# RiskChemi_Sensors_V2_04M1.net
KiCad netlist of a schematic drawn in Altium Designer
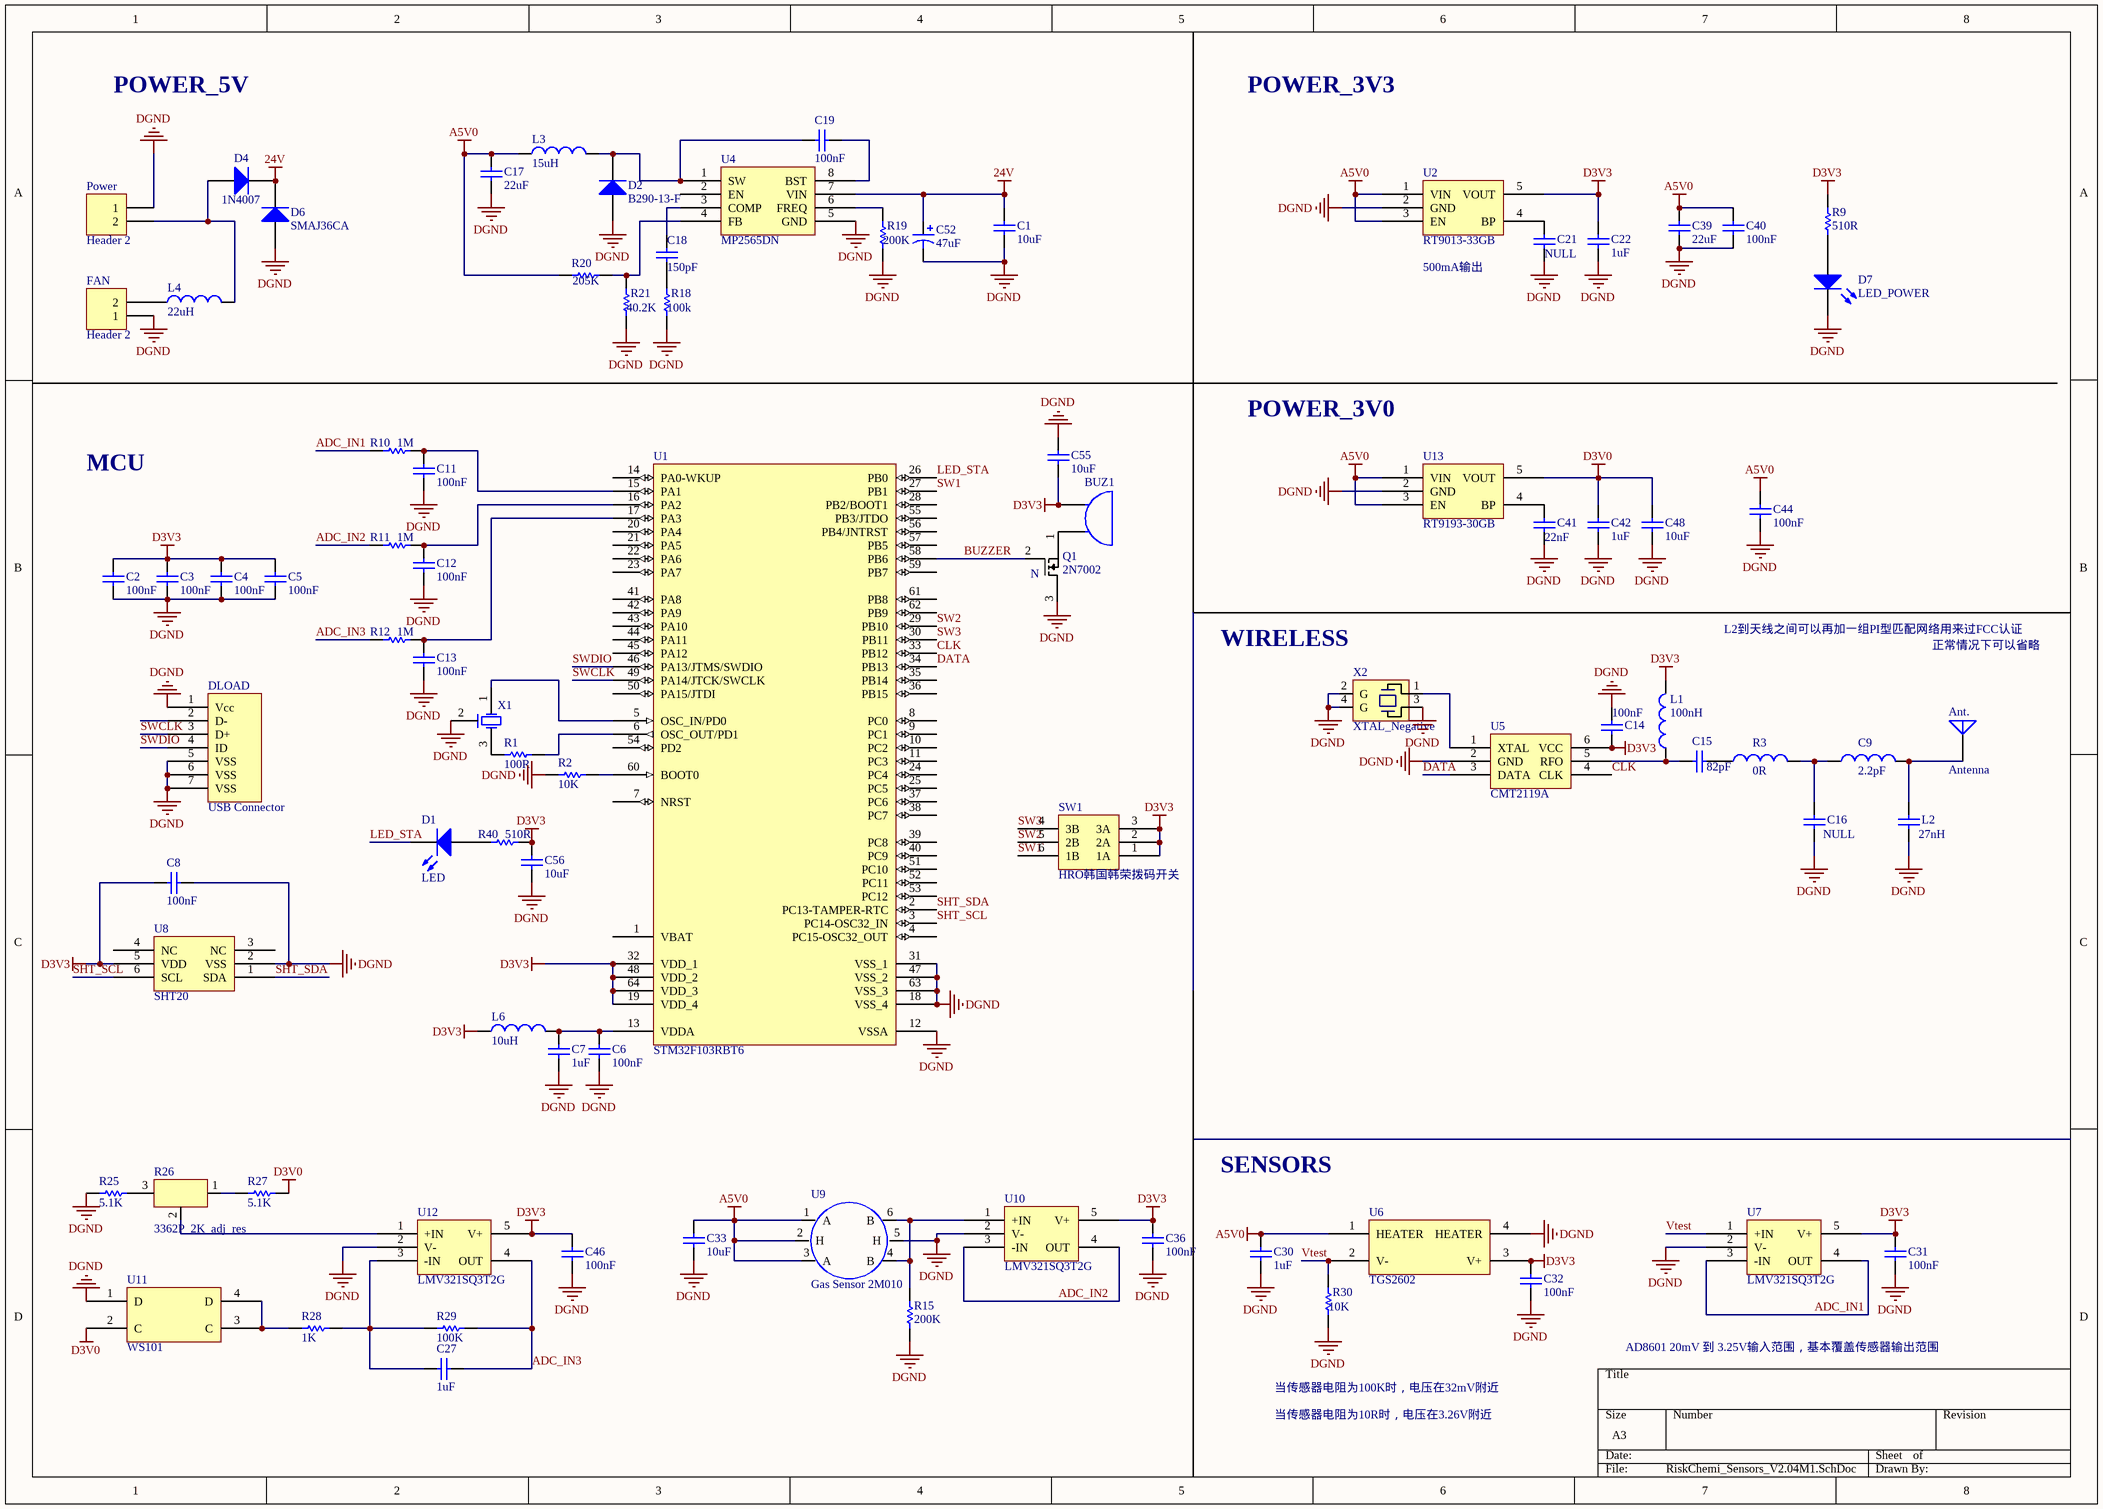
[diagram p0: RiskChemi_Sensors_V2.04M1.SchDoc]

(export (version "E")
  (design (tool "Eeschema 10.0.6"))
  (components
    (comp (ref "Ant.")
      (value "Antenna")
      (footprint "PIN1")
      (description "Generic Antenna")
      (fields (field (name "PUBLISHER") "Altium Limited"))
      (libsource (lib "Miscellaneous Devices") (part "Antenna"))
    )
    (comp (ref "BUZ1")
      (value "BUZZER 0905 through hole")
      (footprint "BUZ0905")
      (description "Buzzer")
      (libsource (lib "杂元件库") (part "BUZZER"))
    )
    (comp (ref "C1")
      (value "10uF")
      (footprint "0805")
      (description "Capacitor,50V")
      (fields (field (name "PUBLISHER") "Altium Limited"))
      (libsource (lib "Miscellaneous Devices") (part "Cap"))
    )
    (comp (ref "C2")
      (value "100nF")
      (footprint "BinFeng:0603")
      (description "Capacitor")
      (fields (field (name "PUBLISHER") "Altium Limited"))
      (libsource (lib "Miscellaneous Devices") (part "Cap"))
    )
    (comp (ref "C3")
      (value "100nF")
      (footprint "BinFeng:0603")
      (description "Capacitor")
      (fields (field (name "PUBLISHER") "Altium Limited"))
      (libsource (lib "Miscellaneous Devices") (part "Cap"))
    )
    (comp (ref "C4")
      (value "100nF")
      (footprint "BinFeng:0603")
      (description "Capacitor")
      (fields (field (name "PUBLISHER") "Altium Limited"))
      (libsource (lib "Miscellaneous Devices") (part "Cap"))
    )
    (comp (ref "C5")
      (value "100nF")
      (footprint "BinFeng:0603")
      (description "Capacitor")
      (fields (field (name "PUBLISHER") "Altium Limited"))
      (libsource (lib "Miscellaneous Devices") (part "Cap"))
    )
    (comp (ref "C6")
      (value "100nF")
      (footprint "BinFeng:0603")
      (description "Capacitor")
      (fields (field (name "PUBLISHER") "Altium Limited"))
      (libsource (lib "Miscellaneous Devices") (part "Cap"))
    )
    (comp (ref "C7")
      (value "1uF")
      (footprint "BinFeng:0603")
      (description "Capacitor")
      (fields (field (name "PUBLISHER") "Altium Limited"))
      (libsource (lib "Miscellaneous Devices") (part "Cap"))
    )
    (comp (ref "C8")
      (value "100nF")
      (footprint "BinFeng:0603")
      (description "Capacitor")
      (fields (field (name "PUBLISHER") "Altium Limited"))
      (libsource (lib "Miscellaneous Devices") (part "Cap"))
    )
    (comp (ref "C9")
      (value "2.2pF")
      (footprint "0603C")
      (description "Inductor")
      (fields (field (name "PUBLISHER") "Altium Limited"))
      (libsource (lib "Miscellaneous Devices") (part "Inductor"))
    )
    (comp (ref "C11")
      (value "100nF")
      (footprint "BinFeng:0603")
      (description "Capacitor")
      (fields (field (name "PUBLISHER") "Altium Limited"))
      (libsource (lib "Miscellaneous Devices") (part "Cap"))
    )
    (comp (ref "C12")
      (value "100nF")
      (footprint "BinFeng:0603")
      (description "Capacitor")
      (fields (field (name "PUBLISHER") "Altium Limited"))
      (libsource (lib "Miscellaneous Devices") (part "Cap"))
    )
    (comp (ref "C13")
      (value "100nF")
      (footprint "BinFeng:0603")
      (description "Capacitor")
      (fields (field (name "PUBLISHER") "Altium Limited"))
      (libsource (lib "Miscellaneous Devices") (part "Cap"))
    )
    (comp (ref "C14")
      (value "100nF")
      (footprint "BinFeng:0402")
      (description "Capacitor")
      (fields (field (name "PUBLISHER") "Altium Limited"))
      (libsource (lib "Miscellaneous Devices") (part "Cap"))
    )
    (comp (ref "C15")
      (value "82pF")
      (footprint "BinFeng:0402")
      (description "Capacitor")
      (fields (field (name "PUBLISHER") "Altium Limited"))
      (libsource (lib "Miscellaneous Devices") (part "Cap"))
    )
    (comp (ref "C16")
      (value "NULL")
      (footprint "BinFeng:0402")
      (description "Capacitor")
      (fields (field (name "PUBLISHER") "Altium Limited"))
      (libsource (lib "Miscellaneous Devices") (part "Cap"))
    )
    (comp (ref "C17")
      (value "22uF")
      (footprint "0805")
      (description "Capacitor,50V")
      (fields (field (name "PUBLISHER") "Altium Limited"))
      (libsource (lib "Miscellaneous Devices") (part "Cap"))
    )
    (comp (ref "C18")
      (value "150pF")
      (footprint "BinFeng:0603")
      (description "Capacitor")
      (fields (field (name "PUBLISHER") "Altium Limited"))
      (libsource (lib "Miscellaneous Devices") (part "Cap"))
    )
    (comp (ref "C19")
      (value "100nF")
      (footprint "BinFeng:0603")
      (description "Capacitor")
      (fields (field (name "PUBLISHER") "Altium Limited"))
      (libsource (lib "Miscellaneous Devices") (part "Cap"))
    )
    (comp (ref "C21")
      (value "NULL")
      (footprint "BinFeng:0402")
      (description "Capacitor")
      (fields (field (name "PUBLISHER") "Altium Limited"))
      (libsource (lib "Miscellaneous Devices") (part "Cap"))
    )
    (comp (ref "C22")
      (value "1uF")
      (footprint "BinFeng:0402")
      (description "Capacitor")
      (fields (field (name "PUBLISHER") "Altium Limited"))
      (libsource (lib "Miscellaneous Devices") (part "Cap"))
    )
    (comp (ref "C27")
      (value "1uF")
      (footprint "BinFeng:0603")
      (description "Capacitor")
      (fields (field (name "PUBLISHER") "Altium Limited"))
      (libsource (lib "Miscellaneous Devices") (part "Cap"))
    )
    (comp (ref "C30")
      (value "1uF")
      (footprint "BinFeng:0603")
      (description "Capacitor")
      (fields (field (name "PUBLISHER") "Altium Limited"))
      (libsource (lib "Miscellaneous Devices") (part "Cap"))
    )
    (comp (ref "C31")
      (value "100nF")
      (footprint "BinFeng:0603")
      (description "Capacitor")
      (fields (field (name "PUBLISHER") "Altium Limited"))
      (libsource (lib "Miscellaneous Devices") (part "Cap"))
    )
    (comp (ref "C32")
      (value "100nF")
      (footprint "BinFeng:0603")
      (description "Capacitor")
      (fields (field (name "PUBLISHER") "Altium Limited"))
      (libsource (lib "Miscellaneous Devices") (part "Cap"))
    )
    (comp (ref "C33")
      (value "10uF")
      (footprint "0805")
      (description "Capacitor")
      (fields (field (name "PUBLISHER") "Altium Limited"))
      (libsource (lib "Miscellaneous Devices") (part "Cap"))
    )
    (comp (ref "C36")
      (value "100nF")
      (footprint "BinFeng:0603")
      (description "Capacitor")
      (fields (field (name "PUBLISHER") "Altium Limited"))
      (libsource (lib "Miscellaneous Devices") (part "Cap"))
    )
    (comp (ref "C39")
      (value "22uF")
      (footprint "1206")
      (description "Capacitor")
      (fields (field (name "PUBLISHER") "Altium Limited"))
      (libsource (lib "Miscellaneous Devices") (part "Cap"))
    )
    (comp (ref "C40")
      (value "100nF")
      (footprint "BinFeng:0402")
      (description "Capacitor")
      (fields (field (name "PUBLISHER") "Altium Limited"))
      (libsource (lib "Miscellaneous Devices") (part "Cap"))
    )
    (comp (ref "C41")
      (value "22nF")
      (footprint "BinFeng:0402")
      (description "Capacitor")
      (fields (field (name "PUBLISHER") "Altium Limited"))
      (libsource (lib "Miscellaneous Devices") (part "Cap"))
    )
    (comp (ref "C42")
      (value "1uF")
      (footprint "BinFeng:0402")
      (description "Capacitor")
      (fields (field (name "PUBLISHER") "Altium Limited"))
      (libsource (lib "Miscellaneous Devices") (part "Cap"))
    )
    (comp (ref "C44")
      (value "100nF")
      (footprint "BinFeng:0402")
      (description "Capacitor")
      (fields (field (name "PUBLISHER") "Altium Limited"))
      (libsource (lib "Miscellaneous Devices") (part "Cap"))
    )
    (comp (ref "C46")
      (value "100nF")
      (footprint "BinFeng:0603")
      (description "Capacitor")
      (fields (field (name "PUBLISHER") "Altium Limited"))
      (libsource (lib "Miscellaneous Devices") (part "Cap"))
    )
    (comp (ref "C48")
      (value "10uF")
      (footprint "0805")
      (description "Capacitor")
      (fields (field (name "PUBLISHER") "Altium Limited"))
      (libsource (lib "Miscellaneous Devices") (part "Cap"))
    )
    (comp (ref "C52")
      (value "47uF")
      (footprint "cap_pol_8*10.2")
      (description "Polarized Capacitor (Radial)")
      (fields (field (name "PUBLISHER") "Altium Limited"))
      (libsource (lib "Miscellaneous Devices") (part "Cap Pol1"))
    )
    (comp (ref "C55")
      (value "10uF")
      (footprint "0805")
      (description "Capacitor")
      (fields (field (name "PUBLISHER") "Altium Limited"))
      (libsource (lib "Miscellaneous Devices") (part "Cap"))
    )
    (comp (ref "C56")
      (value "10uF")
      (footprint "0805")
      (description "Capacitor")
      (fields (field (name "PUBLISHER") "Altium Limited"))
      (libsource (lib "Miscellaneous Devices") (part "Cap"))
    )
    (comp (ref "D1")
      (value "LED")
      (footprint "1206_LED")
      (description "Typical INFRARED GaAs LED")
      (fields (field (name "PUBLISHER") "Altium Limited"))
      (libsource (lib "Miscellaneous Devices") (part "LED0"))
    )
    (comp (ref "D2")
      (value "B290-13-F")
      (footprint "B290")
      (description "Default Diode")
      (fields (field (name "PUBLISHER") "Altium Limited"))
      (libsource (lib "Miscellaneous Devices") (part "Diode"))
    )
    (comp (ref "D4")
      (value "1N4007")
      (footprint "6032_pol")
      (description "1 Amp General Purpose Rectifier")
      (fields (field (name "PUBLISHER") "Altium Limited"))
      (libsource (lib "Miscellaneous Devices") (part "Diode 1N4007"))
    )
    (comp (ref "D6")
      (value "SMAJ36CA")
      (footprint "B290")
      (description "1 Amp General Purpose Rectifier")
      (fields (field (name "PUBLISHER") "Altium Limited"))
      (libsource (lib "Miscellaneous Devices") (part "Diode 1N4007"))
    )
    (comp (ref "D7")
      (value "LED_POWER")
      (footprint "1206_LED")
      (description "Typical INFRARED GaAs LED")
      (fields (field (name "PUBLISHER") "Altium Limited"))
      (libsource (lib "Miscellaneous Devices") (part "LED0"))
    )
    (comp (ref "DLOAD")
      (value "USB Connector")
      (footprint "Mini_USB")
      (libsource (lib "BinFeng_Connectors") (part "Component_1"))
    )
    (comp (ref "FAN")
      (value "Header 2")
      (footprint "HDR1X2")
      (description "Header, 2-Pin")
      (fields (field (name "PUBLISHER") "Altium Limited"))
      (libsource (lib "Miscellaneous Connectors") (part "Header 2"))
    )
    (comp (ref "L1")
      (value "100nH")
      (footprint "0603C")
      (description "Inductor")
      (fields (field (name "PUBLISHER") "Altium Limited"))
      (libsource (lib "Miscellaneous Devices") (part "Inductor"))
    )
    (comp (ref "L2")
      (value "27nH")
      (footprint "BinFeng:0402")
      (description "Capacitor")
      (fields (field (name "PUBLISHER") "Altium Limited"))
      (libsource (lib "Miscellaneous Devices") (part "Cap"))
    )
    (comp (ref "L3")
      (value "15uH")
      (footprint "4*4 Inductor")
      (description "Inductor, 1A")
      (fields (field (name "PUBLISHER") "Altium Limited"))
      (libsource (lib "Miscellaneous Devices") (part "Inductor"))
    )
    (comp (ref "L4")
      (value "22uH")
      (footprint "10*10Inductor")
      (description "Inductor, 1A")
      (fields (field (name "PUBLISHER") "Altium Limited"))
      (libsource (lib "Miscellaneous Devices") (part "Inductor"))
    )
    (comp (ref "L6")
      (value "10uH")
      (footprint "0805")
      (description "Inductor")
      (fields (field (name "PUBLISHER") "Altium Limited"))
      (libsource (lib "Miscellaneous Devices") (part "Inductor"))
    )
    (comp (ref "Power")
      (value "Header 2")
      (footprint "HDR1X2")
      (description "Header, 2-Pin")
      (fields (field (name "PUBLISHER") "Altium Limited"))
      (libsource (lib "") (part "Header 2_1"))
    )
    (comp (ref "Q1") (value "2N7002") (footprint "2N7002") (libsource (lib "seeder") (part "N-MOSFET")))
    (comp (ref "R1")
      (value "100R")
      (footprint "BinFeng:0603")
      (description "Resistor")
      (fields (field (name "PUBLISHER") "Altium Limited"))
      (libsource (lib "Miscellaneous Devices") (part "Res1"))
    )
    (comp (ref "R2")
      (value "10K")
      (footprint "BinFeng:0603")
      (description "Resistor")
      (fields (field (name "PUBLISHER") "Altium Limited"))
      (libsource (lib "Miscellaneous Devices") (part "Res1"))
    )
    (comp (ref "R3")
      (value "0R")
      (footprint "0603C")
      (description "Inductor")
      (fields (field (name "PUBLISHER") "Altium Limited"))
      (libsource (lib "Miscellaneous Devices") (part "Inductor"))
    )
    (comp (ref "R9")
      (value "510R")
      (footprint "BinFeng:0603")
      (description "Resistor")
      (fields (field (name "PUBLISHER") "Altium Limited"))
      (libsource (lib "Miscellaneous Devices") (part "Res1"))
    )
    (comp (ref "R10")
      (value "1M")
      (footprint "BinFeng:0603")
      (description "Resistor")
      (fields (field (name "PUBLISHER") "Altium Limited"))
      (libsource (lib "Miscellaneous Devices") (part "Res1"))
    )
    (comp (ref "R11")
      (value "1M")
      (footprint "BinFeng:0603")
      (description "Resistor")
      (fields (field (name "PUBLISHER") "Altium Limited"))
      (libsource (lib "Miscellaneous Devices") (part "Res1"))
    )
    (comp (ref "R12")
      (value "1M")
      (footprint "BinFeng:0603")
      (description "Resistor")
      (fields (field (name "PUBLISHER") "Altium Limited"))
      (libsource (lib "Miscellaneous Devices") (part "Res1"))
    )
    (comp (ref "R15")
      (value "200K")
      (footprint "BinFeng:0603C")
      (description "Resistor")
      (fields (field (name "Comment") "Res1") (field (name "PUBLISHER") "Altium Limited"))
      (libsource (lib "Miscellaneous Devices") (part "Res1"))
    )
    (comp (ref "R18")
      (value "100k")
      (footprint "BinFeng:0603")
      (description "Resistor")
      (fields (field (name "PUBLISHER") "Altium Limited"))
      (libsource (lib "Miscellaneous Devices") (part "Res1"))
    )
    (comp (ref "R19")
      (value "200K")
      (footprint "BinFeng:0402")
      (description "Resistor")
      (fields (field (name "PUBLISHER") "Altium Limited"))
      (libsource (lib "Miscellaneous Devices") (part "Res1"))
    )
    (comp (ref "R20")
      (value "205K")
      (footprint "BinFeng:0603")
      (description "Resistor")
      (fields (field (name "PUBLISHER") "Altium Limited"))
      (libsource (lib "Miscellaneous Devices") (part "Res1"))
    )
    (comp (ref "R21")
      (value "40.2K")
      (footprint "BinFeng:0603")
      (description "Resistor")
      (fields (field (name "PUBLISHER") "Altium Limited"))
      (libsource (lib "Miscellaneous Devices") (part "Res1"))
    )
    (comp (ref "R25")
      (value "5.1K")
      (footprint "BinFeng:0603")
      (description "Resistor")
      (fields (field (name "PUBLISHER") "Altium Limited"))
      (libsource (lib "Miscellaneous Devices") (part "Res1"))
    )
    (comp (ref "R26")
      (value "3362P_2K_adj_res")
      (footprint "res_adj")
      (libsource (lib "BinFeng_IC") (part "res_adj"))
    )
    (comp (ref "R27")
      (value "5.1K")
      (footprint "BinFeng:0603")
      (description "Resistor")
      (fields (field (name "PUBLISHER") "Altium Limited"))
      (libsource (lib "Miscellaneous Devices") (part "Res1"))
    )
    (comp (ref "R28")
      (value "1K")
      (footprint "BinFeng:0603")
      (description "Resistor")
      (fields (field (name "PUBLISHER") "Altium Limited"))
      (libsource (lib "Miscellaneous Devices") (part "Res1"))
    )
    (comp (ref "R29")
      (value "100K")
      (footprint "BinFeng:0603")
      (description "Resistor")
      (fields (field (name "PUBLISHER") "Altium Limited"))
      (libsource (lib "Miscellaneous Devices") (part "Res1"))
    )
    (comp (ref "R30")
      (value "10K")
      (footprint "BinFeng:0603")
      (description "Resistor")
      (fields (field (name "PUBLISHER") "Altium Limited"))
      (libsource (lib "Miscellaneous Devices") (part "Res1"))
    )
    (comp (ref "R40")
      (value "510R")
      (footprint "BinFeng:0603")
      (description "Resistor")
      (fields (field (name "PUBLISHER") "Altium Limited"))
      (libsource (lib "Miscellaneous Devices") (part "Res1"))
    )
    (comp (ref "SW1")
      (value "HRO韩国韩荣拨码开关")
      (footprint "SW_6P_HRO")
      (libsource (lib "BinFeng_IC") (part "SW_6P"))
    )
    (comp (ref "U1")
      (value "STM32F103RBT6")
      (footprint "LQFP64_N")
      (description "STM32 ARM-based 32-bit MCU with 64 Kbytes Flash, 64-pin LQFP, Industrial Temperature")
      (fields (field (name "PUBLISHER") "Altium Limited"))
      (libsource (lib "ST Microcontroller 32-Bit STM32") (part "STM32F103R8T6"))
    )
    (comp (ref "U2")
      (value "RT9013-33GB")
      (footprint "SOT-23-5")
      (libsource (lib "BinFeng_IC") (part "RT9193"))
    )
    (comp (ref "U4")
      (value "MP2565DN")
      (footprint "so-8")
      (description "DCDC 4.5V~28V input 1.8V ~5V output low power")
      (libsource (lib "BinFeng_IC") (part "MP1584"))
    )
    (comp (ref "U5")
      (value "CMT2119A")
      (footprint "sot23-6")
      (libsource (lib "BinFeng_IC") (part "CMT2119A"))
    )
    (comp (ref "U6")
      (value "TGS2602")
      (footprint "Gas Sensor TGS2602 Slot")
      (description "VOC sensor")
      (libsource (lib "BinFeng_IC") (part "TGS2602"))
    )
    (comp (ref "U7")
      (value "LMV321SQ3T2G")
      (footprint "SC-70-5")
      (libsource (lib "BinFeng_IC") (part "LMV321SQ3T2G"))
    )
    (comp (ref "U8") (value "SHT20") (footprint "SHT20") (libsource (lib "BinFeng_IC") (part "SHT20")))
    (comp (ref "U9")
      (value "Gas Sensor 2M010")
      (footprint "Gas Sensor 2M010 Slot")
      (libsource (lib "BinFeng_IC") (part "Gas Sensor"))
    )
    (comp (ref "U10")
      (value "LMV321SQ3T2G")
      (footprint "SC-70-5")
      (libsource (lib "BinFeng_IC") (part "LMV321SQ3T2G"))
    )
    (comp (ref "U11")
      (value "WS101")
      (footprint "Gas_Sensor_WS101_Slot")
      (libsource (lib "BinFeng_IC") (part "Gas Sensor_WS101"))
    )
    (comp (ref "U12")
      (value "LMV321SQ3T2G")
      (footprint "SC-70-5")
      (libsource (lib "BinFeng_IC") (part "LMV321SQ3T2G"))
    )
    (comp (ref "U13")
      (value "RT9193-30GB")
      (footprint "SOT-23-5")
      (libsource (lib "BinFeng_IC") (part "RT9193"))
    )
    (comp (ref "X1") (value "8M smd") (footprint "8Mhz_XTAL") (libsource (lib "Schlib1") (part "8M smd")))
    (comp (ref "X2")
      (value "XTAL_Negative")
      (footprint "XTAL3225")
      (libsource (lib "BinFeng_IC") (part "XTAL_Negative"))
    )
  )
  (nets
    (net (code "1") (name "/ADC_IN1") (class "Default")
      (node (ref "R10") (pin "1") (pinfunction "1_1") (pintype "passive"))
      (node (ref "U7") (pin "3") (pinfunction "-IN_3") (pintype "passive"))
      (node (ref "U7") (pin "4") (pinfunction "OUT_4") (pintype "passive"))
    )
    (net (code "2") (name "/ADC_IN2") (class "Default")
      (node (ref "R11") (pin "1") (pinfunction "1_1") (pintype "passive"))
      (node (ref "U10") (pin "3") (pinfunction "-IN_3") (pintype "passive"))
      (node (ref "U10") (pin "4") (pinfunction "OUT_4") (pintype "passive"))
    )
    (net (code "3") (name "/ADC_IN3") (class "Default")
      (node (ref "C27") (pin "1") (pinfunction "1_1") (pintype "passive"))
      (node (ref "R12") (pin "1") (pinfunction "1_1") (pintype "passive"))
      (node (ref "R29") (pin "2") (pinfunction "2_2") (pintype "passive"))
      (node (ref "U12") (pin "4") (pinfunction "OUT_4") (pintype "passive"))
    )
    (net (code "4") (name "/BUZZER") (class "Default")
      (node (ref "Q1") (pin "2") (pinfunction "G_2") (pintype "passive"))
      (node (ref "U1") (pin "58") (pinfunction "PB6_58") (pintype "bidirectional"))
    )
    (net (code "5") (name "/CLK") (class "Default")
      (node (ref "U1") (pin "33") (pinfunction "PB12_33") (pintype "bidirectional"))
      (node (ref "U5") (pin "4") (pinfunction "CLK_4") (pintype "passive"))
    )
    (net (code "6") (name "/DATA") (class "Default")
      (node (ref "U1") (pin "34") (pinfunction "PB13_34") (pintype "bidirectional"))
      (node (ref "U5") (pin "3") (pinfunction "DATA_3") (pintype "passive"))
    )
    (net (code "7") (name "/LED_STA") (class "Default")
      (node (ref "D1") (pin "2") (pinfunction "K_2") (pintype "passive"))
      (node (ref "U1") (pin "26") (pinfunction "PB0_26") (pintype "bidirectional"))
    )
    (net (code "8") (name "/SHT_SCL") (class "Default")
      (node (ref "U1") (pin "3") (pinfunction "PC14-OSC32_IN_3") (pintype "bidirectional"))
      (node (ref "U8") (pin "6") (pinfunction "SCL_6") (pintype "passive"))
    )
    (net (code "9") (name "/SHT_SDA") (class "Default")
      (node (ref "U1") (pin "2") (pinfunction "PC13-TAMPER-RTC_2") (pintype "bidirectional"))
      (node (ref "U8") (pin "1") (pinfunction "SDA_1") (pintype "passive"))
    )
    (net (code "10") (name "/SW1") (class "Default")
      (node (ref "SW1") (pin "6") (pinfunction "1B_6") (pintype "passive"))
      (node (ref "U1") (pin "27") (pinfunction "PB1_27") (pintype "bidirectional"))
    )
    (net (code "11") (name "/SW2") (class "Default")
      (node (ref "SW1") (pin "5") (pinfunction "2B_5") (pintype "passive"))
      (node (ref "U1") (pin "29") (pinfunction "PB10_29") (pintype "bidirectional"))
    )
    (net (code "12") (name "/SW3") (class "Default")
      (node (ref "SW1") (pin "4") (pinfunction "3B_4") (pintype "passive"))
      (node (ref "U1") (pin "30") (pinfunction "PB11_30") (pintype "bidirectional"))
    )
    (net (code "13") (name "/SWCLK") (class "Default")
      (node (ref "DLOAD") (pin "3") (pinfunction "D+_3") (pintype "passive"))
      (node (ref "U1") (pin "49") (pinfunction "PA14/JTCK/SWCLK_49") (pintype "bidirectional"))
    )
    (net (code "14") (name "/SWDIO") (class "Default")
      (node (ref "DLOAD") (pin "4") (pinfunction "ID_4") (pintype "passive"))
      (node (ref "U1") (pin "46") (pinfunction "PA13/JTMS/SWDIO_46") (pintype "bidirectional"))
    )
    (net (code "15") (name "/Vtest") (class "Default")
      (node (ref "R30") (pin "2") (pinfunction "2_2") (pintype "passive"))
      (node (ref "U6") (pin "2") (pinfunction "V-_2") (pintype "passive"))
      (node (ref "U7") (pin "1") (pinfunction "+IN_1") (pintype "passive"))
    )
    (net (code "16") (name "24V") (class "Default")
      (node (ref "C1") (pin "2") (pinfunction "2_2") (pintype "passive"))
      (node (ref "C52") (pin "1") (pinfunction "1_1") (pintype "passive"))
      (node (ref "D4") (pin "2") (pinfunction "K_2") (pintype "passive"))
      (node (ref "D6") (pin "2") (pinfunction "K_2") (pintype "passive"))
      (node (ref "U4") (pin "7") (pinfunction "VIN_7") (pintype "passive"))
    )
    (net (code "17") (name "A5V0") (class "Default")
      (node (ref "C17") (pin "2") (pinfunction "2_2") (pintype "passive"))
      (node (ref "C30") (pin "2") (pinfunction "2_2") (pintype "passive"))
      (node (ref "C33") (pin "2") (pinfunction "2_2") (pintype "passive"))
      (node (ref "C39") (pin "1") (pinfunction "1_1") (pintype "passive"))
      (node (ref "C40") (pin "2") (pinfunction "2_2") (pintype "passive"))
      (node (ref "C44") (pin "2") (pinfunction "2_2") (pintype "passive"))
      (node (ref "L3") (pin "1") (pinfunction "1_1") (pintype "passive"))
      (node (ref "R20") (pin "2") (pinfunction "2_2") (pintype "passive"))
      (node (ref "U13") (pin "1") (pinfunction "VIN_1") (pintype "passive"))
      (node (ref "U13") (pin "3") (pinfunction "EN_3") (pintype "passive"))
      (node (ref "U2") (pin "1") (pinfunction "VIN_1") (pintype "passive"))
      (node (ref "U2") (pin "3") (pinfunction "EN_3") (pintype "passive"))
      (node (ref "U6") (pin "1") (pinfunction "HEATER_1") (pintype "passive"))
      (node (ref "U9") (pin "1") (pinfunction "A_1") (pintype "passive"))
      (node (ref "U9") (pin "2") (pinfunction "H_2") (pintype "passive"))
      (node (ref "U9") (pin "3") (pinfunction "A_3") (pintype "passive"))
    )
    (net (code "18") (name "D3V0") (class "Default")
      (node (ref "C42") (pin "2") (pinfunction "2_2") (pintype "passive"))
      (node (ref "C48") (pin "2") (pinfunction "2_2") (pintype "passive"))
      (node (ref "R27") (pin "2") (pinfunction "2_2") (pintype "passive"))
      (node (ref "U11") (pin "2") (pinfunction "C_2") (pintype "passive"))
      (node (ref "U13") (pin "5") (pinfunction "VOUT_5") (pintype "passive"))
    )
    (net (code "19") (name "D3V3") (class "Default")
      (node (ref "BUZ1") (pin "1") (pinfunction "A_1") (pintype "passive"))
      (node (ref "C14") (pin "2") (pinfunction "2_2") (pintype "passive"))
      (node (ref "C2") (pin "2") (pinfunction "2_2") (pintype "passive"))
      (node (ref "C22") (pin "2") (pinfunction "2_2") (pintype "passive"))
      (node (ref "C3") (pin "2") (pinfunction "2_2") (pintype "passive"))
      (node (ref "C31") (pin "2") (pinfunction "2_2") (pintype "passive"))
      (node (ref "C32") (pin "2") (pinfunction "2_2") (pintype "passive"))
      (node (ref "C36") (pin "2") (pinfunction "2_2") (pintype "passive"))
      (node (ref "C4") (pin "2") (pinfunction "2_2") (pintype "passive"))
      (node (ref "C46") (pin "2") (pinfunction "2_2") (pintype "passive"))
      (node (ref "C5") (pin "2") (pinfunction "2_2") (pintype "passive"))
      (node (ref "C55") (pin "2") (pinfunction "2_2") (pintype "passive"))
      (node (ref "C56") (pin "2") (pinfunction "2_2") (pintype "passive"))
      (node (ref "C8") (pin "2") (pinfunction "2_2") (pintype "passive"))
      (node (ref "L1") (pin "2") (pinfunction "2_2") (pintype "passive"))
      (node (ref "L6") (pin "1") (pinfunction "1_1") (pintype "passive"))
      (node (ref "R40") (pin "2") (pinfunction "2_2") (pintype "passive"))
      (node (ref "R9") (pin "2") (pinfunction "2_2") (pintype "passive"))
      (node (ref "SW1") (pin "1") (pinfunction "1A_1") (pintype "passive"))
      (node (ref "SW1") (pin "2") (pinfunction "2A_2") (pintype "passive"))
      (node (ref "SW1") (pin "3") (pinfunction "3A_3") (pintype "passive"))
      (node (ref "U1") (pin "19") (pinfunction "VDD_4_19") (pintype "power_in"))
      (node (ref "U1") (pin "32") (pinfunction "VDD_1_32") (pintype "power_in"))
      (node (ref "U1") (pin "48") (pinfunction "VDD_2_48") (pintype "power_in"))
      (node (ref "U1") (pin "64") (pinfunction "VDD_3_64") (pintype "power_in"))
      (node (ref "U10") (pin "5") (pinfunction "V+_5") (pintype "passive"))
      (node (ref "U12") (pin "5") (pinfunction "V+_5") (pintype "passive"))
      (node (ref "U2") (pin "5") (pinfunction "VOUT_5") (pintype "passive"))
      (node (ref "U5") (pin "6") (pinfunction "VCC_6") (pintype "passive"))
      (node (ref "U6") (pin "3") (pinfunction "V+_3") (pintype "passive"))
      (node (ref "U7") (pin "5") (pinfunction "V+_5") (pintype "passive"))
      (node (ref "U8") (pin "5") (pinfunction "VDD_5") (pintype "passive"))
    )
    (net (code "20") (name "DGND") (class "Default")
      (node (ref "C1") (pin "1") (pinfunction "1_1") (pintype "passive"))
      (node (ref "C11") (pin "2") (pinfunction "2_2") (pintype "passive"))
      (node (ref "C12") (pin "1") (pinfunction "1_1") (pintype "passive"))
      (node (ref "C13") (pin "1") (pinfunction "1_1") (pintype "passive"))
      (node (ref "C14") (pin "1") (pinfunction "1_1") (pintype "passive"))
      (node (ref "C16") (pin "1") (pinfunction "1_1") (pintype "passive"))
      (node (ref "C17") (pin "1") (pinfunction "1_1") (pintype "passive"))
      (node (ref "C2") (pin "1") (pinfunction "1_1") (pintype "passive"))
      (node (ref "C21") (pin "1") (pinfunction "1_1") (pintype "passive"))
      (node (ref "C22") (pin "1") (pinfunction "1_1") (pintype "passive"))
      (node (ref "C3") (pin "1") (pinfunction "1_1") (pintype "passive"))
      (node (ref "C30") (pin "1") (pinfunction "1_1") (pintype "passive"))
      (node (ref "C31") (pin "1") (pinfunction "1_1") (pintype "passive"))
      (node (ref "C32") (pin "1") (pinfunction "1_1") (pintype "passive"))
      (node (ref "C33") (pin "1") (pinfunction "1_1") (pintype "passive"))
      (node (ref "C36") (pin "1") (pinfunction "1_1") (pintype "passive"))
      (node (ref "C39") (pin "2") (pinfunction "2_2") (pintype "passive"))
      (node (ref "C4") (pin "1") (pinfunction "1_1") (pintype "passive"))
      (node (ref "C40") (pin "1") (pinfunction "1_1") (pintype "passive"))
      (node (ref "C41") (pin "1") (pinfunction "1_1") (pintype "passive"))
      (node (ref "C42") (pin "1") (pinfunction "1_1") (pintype "passive"))
      (node (ref "C44") (pin "1") (pinfunction "1_1") (pintype "passive"))
      (node (ref "C46") (pin "1") (pinfunction "1_1") (pintype "passive"))
      (node (ref "C48") (pin "1") (pinfunction "1_1") (pintype "passive"))
      (node (ref "C5") (pin "1") (pinfunction "1_1") (pintype "passive"))
      (node (ref "C52") (pin "2") (pinfunction "2_2") (pintype "passive"))
      (node (ref "C55") (pin "1") (pinfunction "1_1") (pintype "passive"))
      (node (ref "C56") (pin "1") (pinfunction "1_1") (pintype "passive"))
      (node (ref "C6") (pin "1") (pinfunction "1_1") (pintype "passive"))
      (node (ref "C7") (pin "1") (pinfunction "1_1") (pintype "passive"))
      (node (ref "C8") (pin "1") (pinfunction "1_1") (pintype "passive"))
      (node (ref "D2") (pin "1") (pinfunction "A_1") (pintype "passive"))
      (node (ref "D6") (pin "1") (pinfunction "A_1") (pintype "passive"))
      (node (ref "D7") (pin "2") (pinfunction "K_2") (pintype "passive"))
      (node (ref "DLOAD") (pin "1") (pinfunction "Vcc_1") (pintype "passive"))
      (node (ref "DLOAD") (pin "5") (pinfunction "VSS_5") (pintype "passive"))
      (node (ref "DLOAD") (pin "6") (pinfunction "VSS_6") (pintype "passive"))
      (node (ref "DLOAD") (pin "7") (pinfunction "VSS_7") (pintype "passive"))
      (node (ref "FAN") (pin "1") (pinfunction "1_1") (pintype "passive"))
      (node (ref "L2") (pin "1") (pinfunction "1_1") (pintype "passive"))
      (node (ref "Power") (pin "1") (pinfunction "1_1") (pintype "passive"))
      (node (ref "Q1") (pin "3") (pinfunction "S_3") (pintype "passive"))
      (node (ref "R15") (pin "2") (pinfunction "2_2") (pintype "passive"))
      (node (ref "R18") (pin "1") (pinfunction "1_1") (pintype "passive"))
      (node (ref "R19") (pin "1") (pinfunction "1_1") (pintype "passive"))
      (node (ref "R2") (pin "1") (pinfunction "1_1") (pintype "passive"))
      (node (ref "R21") (pin "1") (pinfunction "1_1") (pintype "passive"))
      (node (ref "R25") (pin "1") (pinfunction "1_1") (pintype "passive"))
      (node (ref "R30") (pin "1") (pinfunction "1_1") (pintype "passive"))
      (node (ref "U1") (pin "12") (pinfunction "VSSA_12") (pintype "power_in"))
      (node (ref "U1") (pin "18") (pinfunction "VSS_4_18") (pintype "power_in"))
      (node (ref "U1") (pin "31") (pinfunction "VSS_1_31") (pintype "power_in"))
      (node (ref "U1") (pin "47") (pinfunction "VSS_2_47") (pintype "power_in"))
      (node (ref "U1") (pin "63") (pinfunction "VSS_3_63") (pintype "power_in"))
      (node (ref "U10") (pin "2") (pinfunction "V-_2") (pintype "passive"))
      (node (ref "U11") (pin "1") (pinfunction "D_1") (pintype "passive"))
      (node (ref "U12") (pin "2") (pinfunction "V-_2") (pintype "passive"))
      (node (ref "U13") (pin "2") (pinfunction "GND_2") (pintype "passive"))
      (node (ref "U2") (pin "2") (pinfunction "GND_2") (pintype "passive"))
      (node (ref "U4") (pin "5") (pinfunction "GND_5") (pintype "passive"))
      (node (ref "U5") (pin "2") (pinfunction "GND_2") (pintype "passive"))
      (node (ref "U6") (pin "4") (pinfunction "HEATER_4") (pintype "passive"))
      (node (ref "U7") (pin "2") (pinfunction "V-_2") (pintype "passive"))
      (node (ref "U8") (pin "2") (pinfunction "VSS_2") (pintype "passive"))
      (node (ref "U9") (pin "5") (pinfunction "H_5") (pintype "passive"))
      (node (ref "X1") (pin "2") (pinfunction "GND_2") (pintype "passive"))
      (node (ref "X2") (pin "2") (pinfunction "G_2") (pintype "passive"))
      (node (ref "X2") (pin "3") (pintype "passive"))
      (node (ref "X2") (pin "4") (pinfunction "G_4") (pintype "passive"))
    )
    (net (code "21") (name "Net-(Ant.-A)") (class "Default")
      (node (ref "Ant.") (pin "1") (pinfunction "A_1") (pintype "passive"))
      (node (ref "C9") (pin "2") (pinfunction "2_2") (pintype "passive"))
      (node (ref "L2") (pin "2") (pinfunction "2_2") (pintype "passive"))
    )
    (net (code "22") (name "Net-(BUZ1-B)") (class "Default")
      (node (ref "BUZ1") (pin "2") (pinfunction "B_2") (pintype "passive"))
      (node (ref "Q1") (pin "1") (pinfunction "D_1") (pintype "passive"))
    )
    (net (code "23") (name "Net-(C15-Pad2)") (class "Default")
      (node (ref "C15") (pin "2") (pinfunction "2_2") (pintype "passive"))
      (node (ref "R3") (pin "1") (pinfunction "1_1") (pintype "passive"))
    )
    (net (code "24") (name "Net-(C16-Pad2)") (class "Default")
      (node (ref "C16") (pin "2") (pinfunction "2_2") (pintype "passive"))
      (node (ref "C9") (pin "1") (pinfunction "1_1") (pintype "passive"))
      (node (ref "R3") (pin "2") (pinfunction "2_2") (pintype "passive"))
    )
    (net (code "25") (name "Net-(C18-Pad2)") (class "Default")
      (node (ref "C18") (pin "2") (pinfunction "2_2") (pintype "passive"))
      (node (ref "R18") (pin "2") (pinfunction "2_2") (pintype "passive"))
    )
    (net (code "26") (name "Net-(D1-A)") (class "Default")
      (node (ref "D1") (pin "1") (pinfunction "A_1") (pintype "passive"))
      (node (ref "R40") (pin "1") (pinfunction "1_1") (pintype "passive"))
    )
    (net (code "27") (name "Net-(D2-K)") (class "Default")
      (node (ref "C19") (pin "2") (pinfunction "2_2") (pintype "passive"))
      (node (ref "D2") (pin "2") (pinfunction "K_2") (pintype "passive"))
      (node (ref "L3") (pin "2") (pinfunction "2_2") (pintype "passive"))
      (node (ref "U4") (pin "1") (pinfunction "SW_1") (pintype "passive"))
    )
    (net (code "28") (name "Net-(D4-A)") (class "Default")
      (node (ref "D4") (pin "1") (pinfunction "A_1") (pintype "passive"))
      (node (ref "L4") (pin "2") (pinfunction "2_2") (pintype "passive"))
      (node (ref "Power") (pin "2") (pinfunction "2_2") (pintype "passive"))
    )
    (net (code "29") (name "Net-(D7-A)") (class "Default")
      (node (ref "D7") (pin "1") (pinfunction "A_1") (pintype "passive"))
      (node (ref "R9") (pin "1") (pinfunction "1_1") (pintype "passive"))
    )
    (net (code "30") (name "Net-(FAN-Pad2)") (class "Default")
      (node (ref "FAN") (pin "2") (pinfunction "2_2") (pintype "passive"))
      (node (ref "L4") (pin "1") (pinfunction "1_1") (pintype "passive"))
    )
    (net (code "31") (name "Net-(R25-Pad2)") (class "Default")
      (node (ref "R25") (pin "2") (pinfunction "2_2") (pintype "passive"))
      (node (ref "R26") (pin "3") (pintype "passive"))
    )
    (net (code "32") (name "Net-(R26-Pad1)") (class "Default")
      (node (ref "R26") (pin "1") (pintype "passive"))
      (node (ref "R27") (pin "1") (pinfunction "1_1") (pintype "passive"))
    )
    (net (code "33") (name "Net-(R28-Pad1)") (class "Default")
      (node (ref "R28") (pin "1") (pinfunction "1_1") (pintype "passive"))
      (node (ref "U11") (pin "3") (pinfunction "C_3") (pintype "passive"))
      (node (ref "U11") (pin "4") (pinfunction "D_4") (pintype "passive"))
    )
    (net (code "34") (name "Net-(U1-BOOT0)") (class "Default")
      (node (ref "R2") (pin "2") (pinfunction "2_2") (pintype "passive"))
      (node (ref "U1") (pin "60") (pinfunction "BOOT0_60") (pintype "input"))
    )
    (net (code "35") (name "Net-(U1-OSC_IN{slash}PD0)") (class "Default")
      (node (ref "U1") (pin "5") (pinfunction "OSC_IN/PD0_5") (pintype "input"))
      (node (ref "X1") (pin "1") (pinfunction "OSC1_1") (pintype "passive"))
    )
    (net (code "36") (name "Net-(U1-OSC_OUT{slash}PD1)") (class "Default")
      (node (ref "R1") (pin "2") (pinfunction "2_2") (pintype "passive"))
      (node (ref "U1") (pin "6") (pinfunction "OSC_OUT/PD1_6") (pintype "output"))
    )
    (net (code "37") (name "Net-(U1-PA1)") (class "Default")
      (node (ref "C11") (pin "1") (pinfunction "1_1") (pintype "passive"))
      (node (ref "R10") (pin "2") (pinfunction "2_2") (pintype "passive"))
      (node (ref "U1") (pin "15") (pinfunction "PA1_15") (pintype "bidirectional"))
    )
    (net (code "38") (name "Net-(U1-PA2)") (class "Default")
      (node (ref "C12") (pin "2") (pinfunction "2_2") (pintype "passive"))
      (node (ref "R11") (pin "2") (pinfunction "2_2") (pintype "passive"))
      (node (ref "U1") (pin "16") (pinfunction "PA2_16") (pintype "bidirectional"))
    )
    (net (code "39") (name "Net-(U1-PA3)") (class "Default")
      (node (ref "C13") (pin "2") (pinfunction "2_2") (pintype "passive"))
      (node (ref "R12") (pin "2") (pinfunction "2_2") (pintype "passive"))
      (node (ref "U1") (pin "17") (pinfunction "PA3_17") (pintype "bidirectional"))
    )
    (net (code "40") (name "Net-(U1-VDDA)") (class "Default")
      (node (ref "C6") (pin "2") (pinfunction "2_2") (pintype "passive"))
      (node (ref "C7") (pin "2") (pinfunction "2_2") (pintype "passive"))
      (node (ref "L6") (pin "2") (pinfunction "2_2") (pintype "passive"))
      (node (ref "U1") (pin "13") (pinfunction "VDDA_13") (pintype "power_in"))
    )
    (net (code "41") (name "Net-(U2-BP)") (class "Default")
      (node (ref "C21") (pin "2") (pinfunction "2_2") (pintype "passive"))
      (node (ref "U2") (pin "4") (pinfunction "BP_4") (pintype "passive"))
    )
    (net (code "42") (name "Net-(U4-BST)") (class "Default")
      (node (ref "C19") (pin "1") (pinfunction "1_1") (pintype "passive"))
      (node (ref "U4") (pin "8") (pinfunction "BST_8") (pintype "passive"))
    )
    (net (code "43") (name "Net-(U4-COMP)") (class "Default")
      (node (ref "C18") (pin "1") (pinfunction "1_1") (pintype "passive"))
      (node (ref "U4") (pin "3") (pinfunction "COMP_3") (pintype "passive"))
    )
    (net (code "44") (name "Net-(U4-FB)") (class "Default")
      (node (ref "R20") (pin "1") (pinfunction "1_1") (pintype "passive"))
      (node (ref "R21") (pin "2") (pinfunction "2_2") (pintype "passive"))
      (node (ref "U4") (pin "4") (pinfunction "FB_4") (pintype "passive"))
    )
    (net (code "45") (name "Net-(U4-FREQ)") (class "Default")
      (node (ref "R19") (pin "2") (pinfunction "2_2") (pintype "passive"))
      (node (ref "U4") (pin "6") (pinfunction "FREQ_6") (pintype "passive"))
    )
    (net (code "46") (name "Net-(U5-RFO)") (class "Default")
      (node (ref "C15") (pin "1") (pinfunction "1_1") (pintype "passive"))
      (node (ref "L1") (pin "1") (pinfunction "1_1") (pintype "passive"))
      (node (ref "U5") (pin "5") (pinfunction "RFO_5") (pintype "passive"))
    )
    (net (code "47") (name "Net-(U5-XTAL)") (class "Default")
      (node (ref "U5") (pin "1") (pinfunction "XTAL_1") (pintype "passive"))
      (node (ref "X2") (pin "1") (pintype "passive"))
    )
    (net (code "48") (name "Net-(U10-+IN)") (class "Default")
      (node (ref "R15") (pin "1") (pinfunction "1_1") (pintype "passive"))
      (node (ref "U10") (pin "1") (pinfunction "+IN_1") (pintype "passive"))
      (node (ref "U9") (pin "4") (pinfunction "B_4") (pintype "passive"))
      (node (ref "U9") (pin "6") (pinfunction "B_6") (pintype "passive"))
    )
    (net (code "49") (name "Net-(U12-+IN)") (class "Default")
      (node (ref "R26") (pin "2") (pintype "passive"))
      (node (ref "U12") (pin "1") (pinfunction "+IN_1") (pintype "passive"))
    )
    (net (code "50") (name "Net-(U12--IN)") (class "Default")
      (node (ref "C27") (pin "2") (pinfunction "2_2") (pintype "passive"))
      (node (ref "R28") (pin "2") (pinfunction "2_2") (pintype "passive"))
      (node (ref "R29") (pin "1") (pinfunction "1_1") (pintype "passive"))
      (node (ref "U12") (pin "3") (pinfunction "-IN_3") (pintype "passive"))
    )
    (net (code "51") (name "Net-(U13-BP)") (class "Default")
      (node (ref "C41") (pin "2") (pinfunction "2_2") (pintype "passive"))
      (node (ref "U13") (pin "4") (pinfunction "BP_4") (pintype "passive"))
    )
    (net (code "52") (name "Net-(X1-OSC2)") (class "Default")
      (node (ref "R1") (pin "1") (pinfunction "1_1") (pintype "passive"))
      (node (ref "X1") (pin "3") (pinfunction "OSC2_3") (pintype "passive"))
    )
    (net (code "53") (name "unconnected-(DLOAD-D--Pad2)") (class "Default")
      (node (ref "DLOAD") (pin "2") (pinfunction "D-_2") (pintype "passive"))
    )
    (net (code "54") (name "unconnected-(U1-NRST-Pad7)") (class "Default")
      (node (ref "U1") (pin "7") (pinfunction "NRST_7") (pintype "bidirectional"))
    )
    (net (code "55") (name "unconnected-(U1-PA0-WKUP-Pad14)") (class "Default")
      (node (ref "U1") (pin "14") (pinfunction "PA0-WKUP_14") (pintype "bidirectional"))
    )
    (net (code "56") (name "unconnected-(U1-PA4-Pad20)") (class "Default")
      (node (ref "U1") (pin "20") (pinfunction "PA4_20") (pintype "bidirectional"))
    )
    (net (code "57") (name "unconnected-(U1-PA5-Pad21)") (class "Default")
      (node (ref "U1") (pin "21") (pinfunction "PA5_21") (pintype "bidirectional"))
    )
    (net (code "58") (name "unconnected-(U1-PA6-Pad22)") (class "Default")
      (node (ref "U1") (pin "22") (pinfunction "PA6_22") (pintype "bidirectional"))
    )
    (net (code "59") (name "unconnected-(U1-PA7-Pad23)") (class "Default")
      (node (ref "U1") (pin "23") (pinfunction "PA7_23") (pintype "bidirectional"))
    )
    (net (code "60") (name "unconnected-(U1-PA8-Pad41)") (class "Default")
      (node (ref "U1") (pin "41") (pinfunction "PA8_41") (pintype "bidirectional"))
    )
    (net (code "61") (name "unconnected-(U1-PA9-Pad42)") (class "Default")
      (node (ref "U1") (pin "42") (pinfunction "PA9_42") (pintype "bidirectional"))
    )
    (net (code "62") (name "unconnected-(U1-PA10-Pad43)") (class "Default")
      (node (ref "U1") (pin "43") (pinfunction "PA10_43") (pintype "bidirectional"))
    )
    (net (code "63") (name "unconnected-(U1-PA11-Pad44)") (class "Default")
      (node (ref "U1") (pin "44") (pinfunction "PA11_44") (pintype "bidirectional"))
    )
    (net (code "64") (name "unconnected-(U1-PA12-Pad45)") (class "Default")
      (node (ref "U1") (pin "45") (pinfunction "PA12_45") (pintype "bidirectional"))
    )
    (net (code "65") (name "unconnected-(U1-PA15{slash}JTDI-Pad50)") (class "Default")
      (node (ref "U1") (pin "50") (pinfunction "PA15/JTDI_50") (pintype "bidirectional"))
    )
    (net (code "66") (name "unconnected-(U1-PB2{slash}BOOT1-Pad28)") (class "Default")
      (node (ref "U1") (pin "28") (pinfunction "PB2/BOOT1_28") (pintype "bidirectional"))
    )
    (net (code "67") (name "unconnected-(U1-PB3{slash}JTDO-Pad55)") (class "Default")
      (node (ref "U1") (pin "55") (pinfunction "PB3/JTDO_55") (pintype "bidirectional"))
    )
    (net (code "68") (name "unconnected-(U1-PB4{slash}JNTRST-Pad56)") (class "Default")
      (node (ref "U1") (pin "56") (pinfunction "PB4/JNTRST_56") (pintype "bidirectional"))
    )
    (net (code "69") (name "unconnected-(U1-PB5-Pad57)") (class "Default")
      (node (ref "U1") (pin "57") (pinfunction "PB5_57") (pintype "bidirectional"))
    )
    (net (code "70") (name "unconnected-(U1-PB7-Pad59)") (class "Default")
      (node (ref "U1") (pin "59") (pinfunction "PB7_59") (pintype "bidirectional"))
    )
    (net (code "71") (name "unconnected-(U1-PB8-Pad61)") (class "Default")
      (node (ref "U1") (pin "61") (pinfunction "PB8_61") (pintype "bidirectional"))
    )
    (net (code "72") (name "unconnected-(U1-PB9-Pad62)") (class "Default")
      (node (ref "U1") (pin "62") (pinfunction "PB9_62") (pintype "bidirectional"))
    )
    (net (code "73") (name "unconnected-(U1-PB14-Pad35)") (class "Default")
      (node (ref "U1") (pin "35") (pinfunction "PB14_35") (pintype "bidirectional"))
    )
    (net (code "74") (name "unconnected-(U1-PB15-Pad36)") (class "Default")
      (node (ref "U1") (pin "36") (pinfunction "PB15_36") (pintype "bidirectional"))
    )
    (net (code "75") (name "unconnected-(U1-PC0-Pad8)") (class "Default")
      (node (ref "U1") (pin "8") (pinfunction "PC0_8") (pintype "bidirectional"))
    )
    (net (code "76") (name "unconnected-(U1-PC1-Pad9)") (class "Default")
      (node (ref "U1") (pin "9") (pinfunction "PC1_9") (pintype "bidirectional"))
    )
    (net (code "77") (name "unconnected-(U1-PC2-Pad10)") (class "Default")
      (node (ref "U1") (pin "10") (pinfunction "PC2_10") (pintype "bidirectional"))
    )
    (net (code "78") (name "unconnected-(U1-PC3-Pad11)") (class "Default")
      (node (ref "U1") (pin "11") (pinfunction "PC3_11") (pintype "bidirectional"))
    )
    (net (code "79") (name "unconnected-(U1-PC4-Pad24)") (class "Default")
      (node (ref "U1") (pin "24") (pinfunction "PC4_24") (pintype "bidirectional"))
    )
    (net (code "80") (name "unconnected-(U1-PC5-Pad25)") (class "Default")
      (node (ref "U1") (pin "25") (pinfunction "PC5_25") (pintype "bidirectional"))
    )
    (net (code "81") (name "unconnected-(U1-PC6-Pad37)") (class "Default")
      (node (ref "U1") (pin "37") (pinfunction "PC6_37") (pintype "bidirectional"))
    )
    (net (code "82") (name "unconnected-(U1-PC7-Pad38)") (class "Default")
      (node (ref "U1") (pin "38") (pinfunction "PC7_38") (pintype "bidirectional"))
    )
    (net (code "83") (name "unconnected-(U1-PC8-Pad39)") (class "Default")
      (node (ref "U1") (pin "39") (pinfunction "PC8_39") (pintype "bidirectional"))
    )
    (net (code "84") (name "unconnected-(U1-PC9-Pad40)") (class "Default")
      (node (ref "U1") (pin "40") (pinfunction "PC9_40") (pintype "bidirectional"))
    )
    (net (code "85") (name "unconnected-(U1-PC10-Pad51)") (class "Default")
      (node (ref "U1") (pin "51") (pinfunction "PC10_51") (pintype "bidirectional"))
    )
    (net (code "86") (name "unconnected-(U1-PC11-Pad52)") (class "Default")
      (node (ref "U1") (pin "52") (pinfunction "PC11_52") (pintype "bidirectional"))
    )
    (net (code "87") (name "unconnected-(U1-PC12-Pad53)") (class "Default")
      (node (ref "U1") (pin "53") (pinfunction "PC12_53") (pintype "bidirectional"))
    )
    (net (code "88") (name "unconnected-(U1-PC15-OSC32_OUT-Pad4)") (class "Default")
      (node (ref "U1") (pin "4") (pinfunction "PC15-OSC32_OUT_4") (pintype "bidirectional"))
    )
    (net (code "89") (name "unconnected-(U1-PD2-Pad54)") (class "Default")
      (node (ref "U1") (pin "54") (pinfunction "PD2_54") (pintype "bidirectional"))
    )
    (net (code "90") (name "unconnected-(U1-VBAT-Pad1)") (class "Default")
      (node (ref "U1") (pin "1") (pinfunction "VBAT_1") (pintype "power_in"))
    )
    (net (code "91") (name "unconnected-(U4-EN-Pad2)") (class "Default")
      (node (ref "U4") (pin "2") (pinfunction "EN_2") (pintype "passive"))
    )
    (net (code "92") (name "unconnected-(U8-NC-Pad3)") (class "Default")
      (node (ref "U8") (pin "3") (pinfunction "NC_3") (pintype "passive"))
    )
    (net (code "93") (name "unconnected-(U8-NC-Pad4)") (class "Default")
      (node (ref "U8") (pin "4") (pinfunction "NC_4") (pintype "passive"))
    )
  )
)
